# HeatSink.net
KiCad netlist of a schematic drawn in Altium Designer
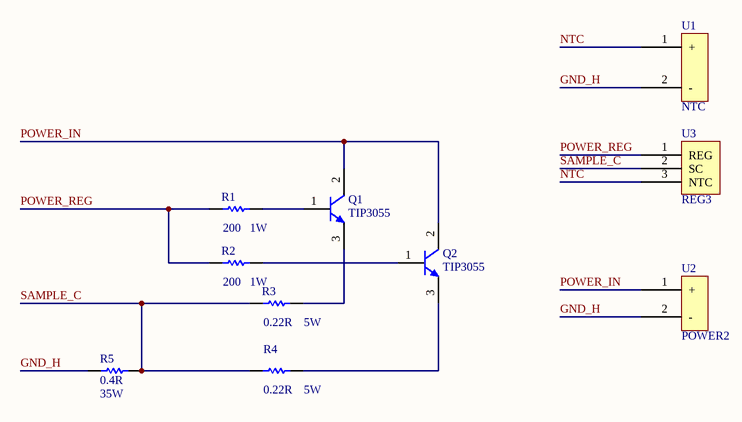
[diagram p0: HeatSink.SchDoc]

(export (version "E")
  (design (tool "Eeschema 10.0.6"))
  (components
    (comp (ref "Q1")
      (value "TIP3055")
      (footprint "CNCPowerSupply:TO-247-ZUO")
      (description "NPN Bipolar Transistor")
      (fields (field (name "PUBLISHER") "Altium Limited"))
      (libsource (lib "Miscellaneous Devices") (part "NPN"))
    )
    (comp (ref "Q2")
      (value "TIP3055")
      (footprint "CNCPowerSupply:TO-247-ZUO")
      (description "NPN Bipolar Transistor")
      (fields (field (name "PUBLISHER") "Altium Limited"))
      (libsource (lib "Miscellaneous Devices") (part "NPN"))
    )
    (comp (ref "R1")
      (value "1W")
      (footprint "CNCPowerSupply:AXIAL-0.7")
      (description "Resistor")
      (fields (field (name "ALTIUM_VALUE") "200") (field (name "PUBLISHER") "Altium Limited"))
      (libsource (lib "Miscellaneous Devices") (part "Res1"))
    )
    (comp (ref "R2")
      (value "1W")
      (footprint "CNCPowerSupply:AXIAL-0.7")
      (description "Resistor")
      (fields (field (name "ALTIUM_VALUE") "200") (field (name "PUBLISHER") "Altium Limited"))
      (libsource (lib "Miscellaneous Devices") (part "Res1"))
    )
    (comp (ref "R3")
      (value "5W")
      (footprint "CNCPowerSupply:AXIAL-0.4")
      (description "Resistor")
      (fields (field (name "ALTIUM_VALUE") "0.22R") (field (name "PUBLISHER") "Altium Limited"))
      (libsource (lib "Miscellaneous Devices") (part "Res1"))
    )
    (comp (ref "R4")
      (value "5W")
      (footprint "CNCPowerSupply:AXIAL-0.4")
      (description "Resistor")
      (fields (field (name "ALTIUM_VALUE") "0.22R") (field (name "PUBLISHER") "Altium Limited"))
      (libsource (lib "Miscellaneous Devices") (part "Res1"))
    )
    (comp (ref "R5")
      (value "35W")
      (footprint "CNCPowerSupply:TO-220AB - 2 Legs")
      (description "Resistor")
      (fields (field (name "ALTIUM_VALUE") "0.4R") (field (name "PUBLISHER") "Altium Limited"))
      (libsource (lib "Miscellaneous Devices") (part "Res1"))
    )
    (comp (ref "U1")
      (value "NTC")
      (footprint "CNCPowerSupply:X254-2P")
      (libsource (lib "CNCPowerSupply") (part "NTC"))
    )
    (comp (ref "U2")
      (value "POWER2")
      (footprint "CNCPowerSupply:KF128-50-2P")
      (libsource (lib "CNCPowerSupply") (part "POWER2"))
    )
    (comp (ref "U3")
      (value "REG3")
      (footprint "CNCPowerSupply:X254-3P")
      (description "REG2")
      (libsource (lib "CNCPowerSupply") (part "REG3"))
    )
  )
  (nets
    (net (code "1") (name "/GND_H") (class "Default")
      (node (ref "R5") (pin "2") (pinfunction "2_2") (pintype "passive"))
      (node (ref "U1") (pin "2") (pinfunction "-_2") (pintype "passive"))
      (node (ref "U2") (pin "2") (pinfunction "-_2") (pintype "passive"))
    )
    (net (code "2") (name "/NTC") (class "Default")
      (node (ref "U1") (pin "1") (pinfunction "+_1") (pintype "passive"))
      (node (ref "U3") (pin "3") (pinfunction "NTC_3") (pintype "passive"))
    )
    (net (code "3") (name "/POWER_IN") (class "Default")
      (node (ref "Q1") (pin "2") (pinfunction "C_2") (pintype "passive"))
      (node (ref "Q2") (pin "2") (pinfunction "C_2") (pintype "passive"))
      (node (ref "U2") (pin "1") (pinfunction "+_1") (pintype "passive"))
    )
    (net (code "4") (name "/POWER_REG") (class "Default")
      (node (ref "R1") (pin "2") (pinfunction "2_2") (pintype "passive"))
      (node (ref "R2") (pin "2") (pinfunction "2_2") (pintype "passive"))
      (node (ref "U3") (pin "1") (pinfunction "REG_1") (pintype "passive"))
    )
    (net (code "5") (name "/SAMPLE_C") (class "Default")
      (node (ref "R3") (pin "2") (pinfunction "2_2") (pintype "passive"))
      (node (ref "R4") (pin "2") (pinfunction "2_2") (pintype "passive"))
      (node (ref "R5") (pin "1") (pinfunction "1_1") (pintype "passive"))
      (node (ref "U3") (pin "2") (pinfunction "SC_2") (pintype "passive"))
    )
    (net (code "6") (name "Net-(Q1-B)") (class "Default")
      (node (ref "Q1") (pin "1") (pinfunction "B_1") (pintype "passive"))
      (node (ref "R1") (pin "1") (pinfunction "1_1") (pintype "passive"))
    )
    (net (code "7") (name "Net-(Q1-E)") (class "Default")
      (node (ref "Q1") (pin "3") (pinfunction "E_3") (pintype "passive"))
      (node (ref "R3") (pin "1") (pinfunction "1_1") (pintype "passive"))
    )
    (net (code "8") (name "Net-(Q2-B)") (class "Default")
      (node (ref "Q2") (pin "1") (pinfunction "B_1") (pintype "passive"))
      (node (ref "R2") (pin "1") (pinfunction "1_1") (pintype "passive"))
    )
    (net (code "9") (name "Net-(Q2-E)") (class "Default")
      (node (ref "Q2") (pin "3") (pinfunction "E_3") (pintype "passive"))
      (node (ref "R4") (pin "1") (pinfunction "1_1") (pintype "passive"))
    )
  )
)
